# SingleBoardControlRev1.net
KiCad netlist of a schematic drawn in Altium Designer
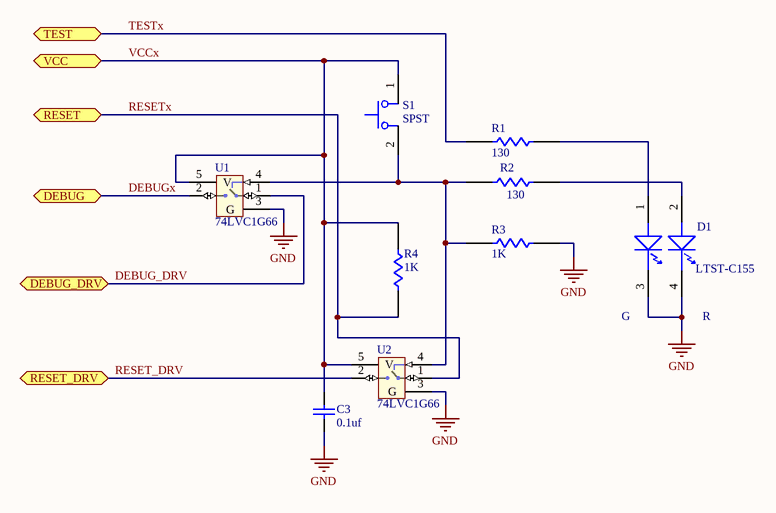
[diagram p0: SingleBoardControlRev1.SchDoc]

(export (version "E")
  (design (tool "Eeschema 10.0.6"))
  (components
    (comp (ref "C3")
      (value "0.1uf")
      (footprint "0603_072205")
      (description "Capacitor")
      (fields (field (name "PARTNO") "C0603C104Z3VACTU"))
      (libsource (lib "Miscellaneous Devices") (part "Cap"))
    )
    (comp (ref "D1")
      (value "LTST-C155")
      (footprint "LED 5mm x 2.5mm_061112")
      (fields (field (name "PARTNO") "LTST-C155GEKT"))
      (libsource (lib "Discrete") (part "LED_BI_2_1"))
    )
    (comp (ref "R1")
      (value "130")
      (footprint "0603_072205")
      (fields (field (name "PARTNO") "MCR03EZPFX1300"))
      (libsource (lib "Discrete") (part "RESISTOR"))
    )
    (comp (ref "R2")
      (value "130")
      (footprint "0603_072205")
      (fields (field (name "PARTNO") "MCR03EZPFX1300"))
      (libsource (lib "Discrete") (part "RESISTOR"))
    )
    (comp (ref "R3")
      (value "1K")
      (footprint "0603_072205")
      (fields (field (name "PARTNO") "MCR03EZPFX1001"))
      (libsource (lib "Discrete") (part "RESISTOR"))
    )
    (comp (ref "R4")
      (value "1K")
      (footprint "0603_072205")
      (fields (field (name "PARTNO") "MCR03EZPFX1001"))
      (libsource (lib "Discrete") (part "RESISTOR"))
    )
    (comp (ref "S1")
      (value "SPST")
      (footprint "SwitchDPDT_6_061412")
      (fields (field (name "PARTNO") "PVA2 EE H1"))
      (libsource (lib "Common") (part "SWITCH PB"))
    )
    (comp (ref "U1")
      (value "74LVC1G66")
      (footprint "SOT25_030205")
      (description "Single Solid State Switch")
      (fields (field (name "PARTNO") "SN74LVC1G66DBVR"))
      (libsource (lib "Common") (part "7466_SINGLE"))
    )
    (comp (ref "U2")
      (value "74LVC1G66")
      (footprint "SOT25_030205")
      (description "Single Solid State Switch")
      (fields (field (name "PARTNO") "SN74LVC1G66DBVR"))
      (libsource (lib "Common") (part "7466_SINGLE"))
    )
  )
  (nets
    (net (code "1") (name "/DEBUG_DRV") (class "Default")
      (node (ref "U1") (pin "1") (pinfunction "INA_1") (pintype "bidirectional"))
    )
    (net (code "2") (name "/DEBUGx") (class "Default")
      (node (ref "U1") (pin "2") (pinfunction "OUTY_2") (pintype "bidirectional"))
    )
    (net (code "3") (name "/RESET_DRV") (class "Default")
      (node (ref "U2") (pin "2") (pinfunction "OUTY_2") (pintype "bidirectional"))
    )
    (net (code "4") (name "/RESETx") (class "Default")
      (node (ref "R4") (pin "2") (pinfunction "2_2") (pintype "passive"))
      (node (ref "U2") (pin "1") (pinfunction "INA_1") (pintype "bidirectional"))
    )
    (net (code "5") (name "/TESTx") (class "Default")
      (node (ref "R1") (pin "2") (pinfunction "2_2") (pintype "passive"))
    )
    (net (code "6") (name "/VCCx") (class "Default")
      (node (ref "C3") (pin "1") (pinfunction "1_1") (pintype "passive"))
      (node (ref "R4") (pin "1") (pinfunction "1_1") (pintype "passive"))
      (node (ref "S1") (pin "1") (pinfunction "1_1") (pintype "passive"))
      (node (ref "U1") (pin "5") (pinfunction "V_5") (pintype "power_in"))
      (node (ref "U2") (pin "5") (pinfunction "V_5") (pintype "power_in"))
    )
    (net (code "7") (name "GND") (class "Default")
      (node (ref "C3") (pin "2") (pinfunction "2_2") (pintype "passive"))
      (node (ref "D1") (pin "3") (pinfunction "K_3") (pintype "passive"))
      (node (ref "D1") (pin "4") (pinfunction "K_4") (pintype "passive"))
      (node (ref "R3") (pin "2") (pinfunction "2_2") (pintype "passive"))
      (node (ref "U1") (pin "3") (pinfunction "G_3") (pintype "power_in"))
      (node (ref "U2") (pin "3") (pinfunction "G_3") (pintype "power_in"))
    )
    (net (code "8") (name "Net-(D1-G)") (class "Default")
      (node (ref "D1") (pin "1") (pinfunction "G_1") (pintype "passive"))
      (node (ref "R1") (pin "1") (pinfunction "1_1") (pintype "passive"))
    )
    (net (code "9") (name "Net-(D1-R)") (class "Default")
      (node (ref "D1") (pin "2") (pinfunction "R_2") (pintype "passive"))
      (node (ref "R2") (pin "1") (pinfunction "1_1") (pintype "passive"))
    )
    (net (code "10") (name "Net-(U1-EN)") (class "Default")
      (node (ref "R2") (pin "2") (pinfunction "2_2") (pintype "passive"))
      (node (ref "R3") (pin "1") (pinfunction "1_1") (pintype "passive"))
      (node (ref "S1") (pin "2") (pinfunction "2_2") (pintype "passive"))
      (node (ref "U1") (pin "4") (pinfunction "EN_4") (pintype "input"))
      (node (ref "U2") (pin "4") (pinfunction "EN_4") (pintype "input"))
    )
  )
)
